# DriverPCB.net
KiCad netlist of a schematic drawn in Altium Designer
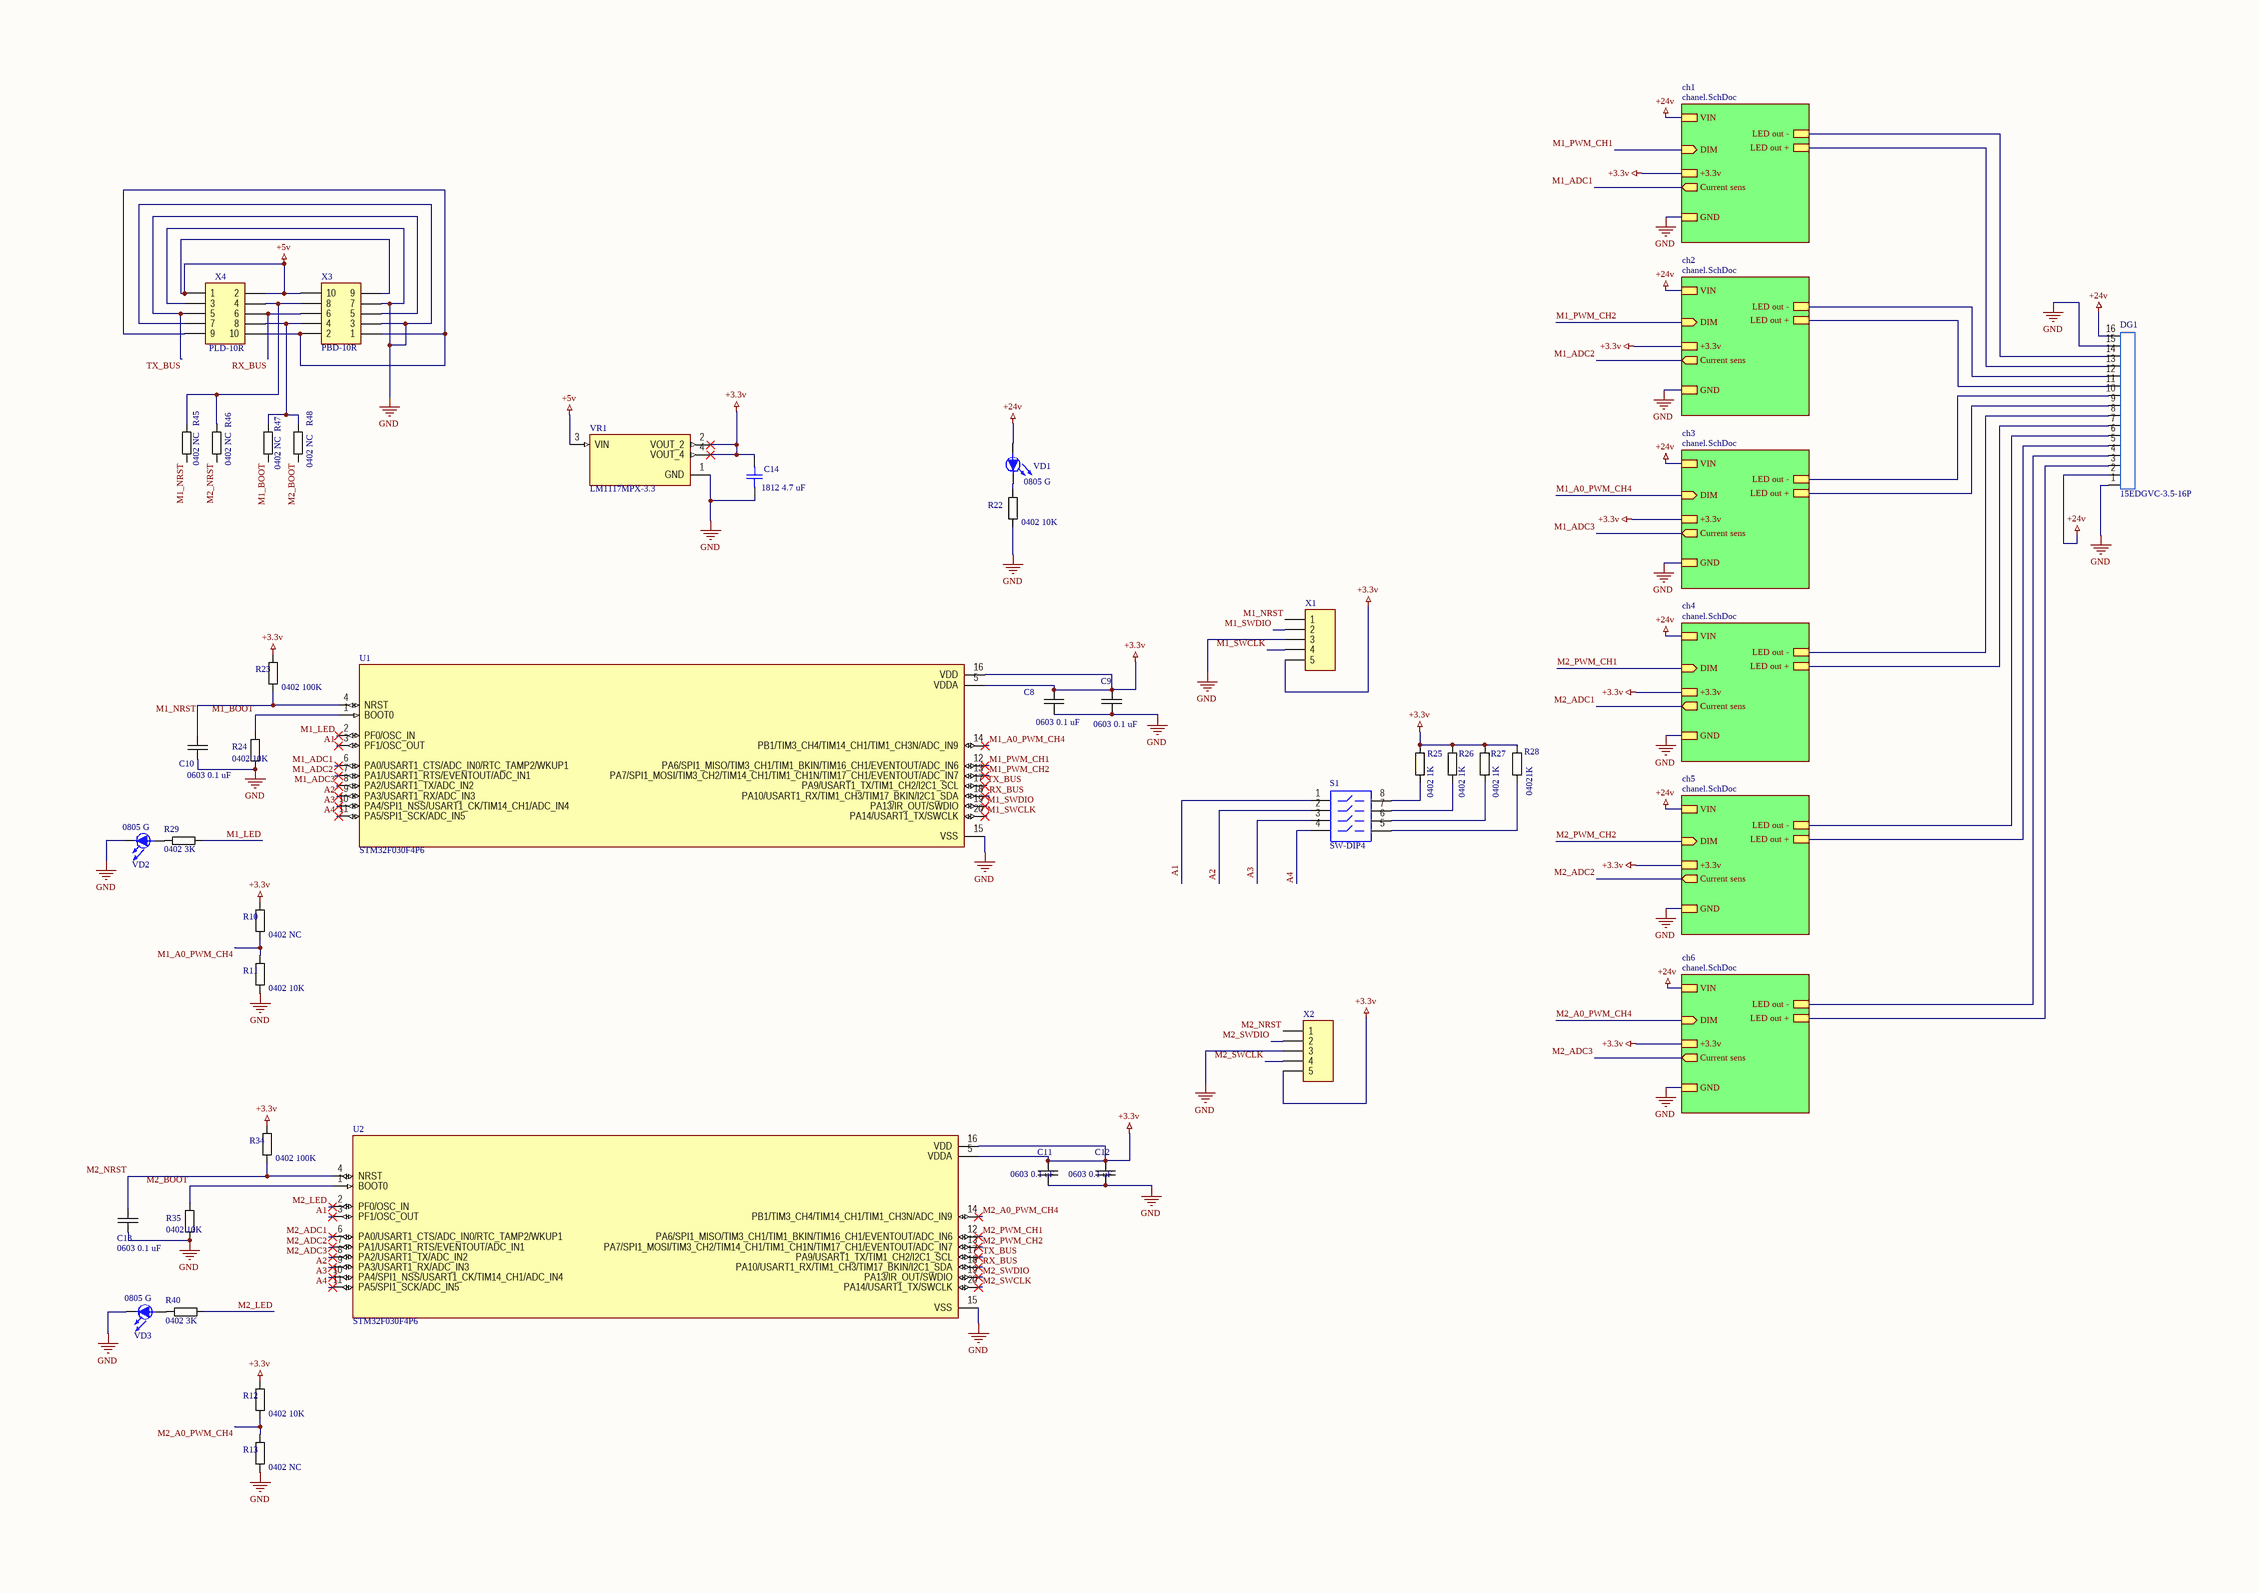
[diagram p0: DriverPCB.SchDoc]

(export (version "E")
  (design (tool "Eeschema 10.0.6"))
  (components
    (comp (ref "C8")
      (value "0603 0.1 uF")
      (footprint "CAPACITOR 0603")
      (description "Ceramic Capacitor")
      (libsource (lib "Maks_lib") (part "Capasitor"))
    )
    (comp (ref "C9")
      (value "0603 0.1 uF")
      (footprint "CAPACITOR 0603")
      (description "Ceramic Capacitor")
      (libsource (lib "Maks_lib") (part "Capasitor"))
    )
    (comp (ref "C10")
      (value "0603 0.1 uF")
      (footprint "CAPACITOR 0603")
      (description "Ceramic Capacitor")
      (libsource (lib "Maks_lib") (part "Capasitor"))
    )
    (comp (ref "C11")
      (value "0603 0.1 uF")
      (footprint "CAPACITOR 0603")
      (description "Ceramic Capacitor")
      (libsource (lib "Maks_lib") (part "Capasitor"))
    )
    (comp (ref "C12")
      (value "0603 0.1 uF")
      (footprint "CAPACITOR 0603")
      (description "Ceramic Capacitor")
      (libsource (lib "Maks_lib") (part "Capasitor"))
    )
    (comp (ref "C13")
      (value "0603 0.1 uF")
      (footprint "CAPACITOR 0603")
      (description "Ceramic Capacitor")
      (libsource (lib "Maks_lib") (part "Capasitor"))
    )
    (comp (ref "C14")
      (value "1812 4.7 uF")
      (footprint "CAPCHIP1812")
      (description "Ceramic Capacitor")
      (libsource (lib "RCL") (part "Cap C"))
    )
    (comp (ref "DG1")
      (value "15EDGVC-3.5-16P")
      (footprint "15EDGVC-3.5-16P")
      (libsource (lib "Degson") (part "15EDGVC-3.5-16P"))
    )
    (comp (ref "R10")
      (value "0402 NC")
      (footprint "Resistor 0402")
      (description "Resistor")
      (libsource (lib "Maks_lib") (part "Resistor"))
    )
    (comp (ref "R11")
      (value "0402 10K")
      (footprint "Resistor 0402")
      (description "Resistor")
      (libsource (lib "Maks_lib") (part "Resistor"))
    )
    (comp (ref "R12")
      (value "0402 10K")
      (footprint "Resistor 0402")
      (description "Resistor")
      (libsource (lib "Maks_lib") (part "Resistor"))
    )
    (comp (ref "R13")
      (value "0402 NC")
      (footprint "Resistor 0402")
      (description "Resistor")
      (libsource (lib "Maks_lib") (part "Resistor"))
    )
    (comp (ref "R22")
      (value "0402 10K")
      (footprint "Resistor 0402")
      (description "Resistor")
      (libsource (lib "Maks_lib") (part "Resistor"))
    )
    (comp (ref "R23")
      (value "0402 100K")
      (footprint "Resistor 0402")
      (description "Resistor")
      (libsource (lib "Maks_lib") (part "Resistor"))
    )
    (comp (ref "R24")
      (value "0402 10K")
      (footprint "Resistor 0402")
      (description "Resistor")
      (libsource (lib "Maks_lib") (part "Resistor"))
    )
    (comp (ref "R25")
      (value "0402 1K")
      (footprint "Resistor 0402")
      (description "Resistor")
      (libsource (lib "Maks_lib") (part "Resistor"))
    )
    (comp (ref "R26")
      (value "0402 1K")
      (footprint "Resistor 0402")
      (description "Resistor")
      (libsource (lib "Maks_lib") (part "Resistor"))
    )
    (comp (ref "R27")
      (value "0402 1K")
      (footprint "Resistor 0402")
      (description "Resistor")
      (libsource (lib "Maks_lib") (part "Resistor"))
    )
    (comp (ref "R28")
      (value "04021K")
      (footprint "Resistor 0402")
      (description "Resistor")
      (libsource (lib "Maks_lib") (part "Resistor"))
    )
    (comp (ref "R29")
      (value "0402 3K")
      (footprint "Resistor 0402")
      (description "Resistor")
      (libsource (lib "Maks_lib") (part "Resistor"))
    )
    (comp (ref "R34")
      (value "0402 100K")
      (footprint "Resistor 0402")
      (description "Resistor")
      (libsource (lib "Maks_lib") (part "Resistor"))
    )
    (comp (ref "R35")
      (value "0402 10K")
      (footprint "Resistor 0402")
      (description "Resistor")
      (libsource (lib "Maks_lib") (part "Resistor"))
    )
    (comp (ref "R40")
      (value "0402 3K")
      (footprint "Resistor 0402")
      (description "Resistor")
      (libsource (lib "Maks_lib") (part "Resistor"))
    )
    (comp (ref "R45")
      (value "0402 NC")
      (footprint "Resistor 0402")
      (description "Resistor")
      (libsource (lib "Maks_lib") (part "Resistor"))
    )
    (comp (ref "R46")
      (value "0402 NC")
      (footprint "Resistor 0402")
      (description "Resistor")
      (libsource (lib "Maks_lib") (part "Resistor"))
    )
    (comp (ref "R47")
      (value "0402 NC")
      (footprint "Resistor 0402")
      (description "Resistor")
      (libsource (lib "Maks_lib") (part "Resistor"))
    )
    (comp (ref "R48")
      (value "0402 NC")
      (footprint "Resistor 0402")
      (description "Resistor")
      (libsource (lib "Maks_lib") (part "Resistor"))
    )
    (comp (ref "S1")
      (value "SW-DIP4")
      (footprint "DIP-8")
      (description "DIP Switch")
      (fields (field (name "PUBLISHER") "Altium Limited"))
      (libsource (lib "Miscellaneous Devices") (part "SW-DIP4"))
    )
    (comp (ref "U1")
      (value "STM32F030F4P6")
      (footprint "SOP65P640X120-20N")
      (description "MCU 32-bit STM32F ARM Cortex M0 RISC 16KB Flash 2.5V/3.3V 20-Pin TSSOP Tray")
      (libsource (lib "STM32F030F4P6") (part "STM32F030F4P6"))
    )
    (comp (ref "U2")
      (value "STM32F030F4P6")
      (footprint "SOP65P640X120-20N")
      (description "MCU 32-bit STM32F ARM Cortex M0 RISC 16KB Flash 2.5V/3.3V 20-Pin TSSOP Tray")
      (libsource (lib "STM32F030F4P6") (part "STM32F030F4P6"))
    )
    (comp (ref "VD1")
      (value "0805 G")
      (footprint "0805-")
      (description "Green")
      (libsource (lib "DT") (part "LED SMD"))
    )
    (comp (ref "VD2")
      (value "0805 G")
      (footprint "0805-")
      (description "Green")
      (libsource (lib "DT") (part "LED SMD"))
    )
    (comp (ref "VD3")
      (value "0805 G")
      (footprint "0805-")
      (description "Green")
      (libsource (lib "DT") (part "LED SMD"))
    )
    (comp (ref "VR1")
      (value "LM1117MPX-3.3")
      (footprint "VREG_LM1117MPX-3.3")
      (description "800-mA 15-V linear voltage regulator")
      (fields (field (name "MF") "Texas Instruments"))
      (libsource (lib "LM1117MPX-3.3") (part "LM1117MPX-3.3"))
    )
    (comp (ref "X1")
      (value "~")
      (footprint "PLS-5-3D")
      (description "Header, 5-Pin")
      (fields (field (name "PARTNUMBER") "PLS-5"))
      (libsource (lib "AX_Altium_v2.3") (part "PLS-5"))
    )
    (comp (ref "X2")
      (value "~")
      (footprint "PLS-5-3D")
      (description "Header, 5-Pin")
      (fields (field (name "PARTNUMBER") "PLS-5"))
      (libsource (lib "AX_Altium_v2.3") (part "PLS-5"))
    )
    (comp (ref "X3")
      (value "PBD-10R")
      (footprint "PBD-10RR")
      (description "Header, 5-Pin, Dual row")
      (libsource (lib "AX_Altium_v2.3") (part "PBD-10R"))
    )
    (comp (ref "X4")
      (value "PLD-10R")
      (footprint "PLD-10RR2")
      (description "Header, 5-Pin, Dual row")
      (libsource (lib "AX_Altium_v2.3") (part "PLD-10R"))
    )
  )
  (nets
    (net (code "1") (name "+3.3v") (class "Default")
      (node (ref "C11") (pin "1") (pinfunction "1_1") (pintype "passive"))
      (node (ref "C12") (pin "1") (pinfunction "1_1") (pintype "passive"))
      (node (ref "C14") (pin "2") (pinfunction "2_2") (pintype "passive"))
      (node (ref "C8") (pin "1") (pinfunction "1_1") (pintype "passive"))
      (node (ref "C9") (pin "1") (pinfunction "1_1") (pintype "passive"))
      (node (ref "R10") (pin "2") (pinfunction "2_2") (pintype "passive"))
      (node (ref "R12") (pin "2") (pinfunction "2_2") (pintype "passive"))
      (node (ref "R23") (pin "2") (pinfunction "2_2") (pintype "passive"))
      (node (ref "R25") (pin "1") (pinfunction "1_1") (pintype "passive"))
      (node (ref "R26") (pin "1") (pinfunction "1_1") (pintype "passive"))
      (node (ref "R27") (pin "1") (pinfunction "1_1") (pintype "passive"))
      (node (ref "R28") (pin "1") (pinfunction "1_1") (pintype "passive"))
      (node (ref "R34") (pin "2") (pinfunction "2_2") (pintype "passive"))
      (node (ref "U1") (pin "16") (pinfunction "VDD_16") (pintype "power_in"))
      (node (ref "U1") (pin "5") (pinfunction "VDDA_5") (pintype "power_in"))
      (node (ref "U2") (pin "16") (pinfunction "VDD_16") (pintype "power_in"))
      (node (ref "U2") (pin "5") (pinfunction "VDDA_5") (pintype "power_in"))
      (node (ref "VR1") (pin "2") (pinfunction "VOUT_2_2") (pintype "output"))
      (node (ref "VR1") (pin "4") (pinfunction "VOUT_4_4") (pintype "output"))
      (node (ref "X1") (pin "5") (pinfunction "5_5") (pintype "passive"))
      (node (ref "X2") (pin "5") (pinfunction "5_5") (pintype "passive"))
    )
    (net (code "2") (name "+5v") (class "Default")
      (node (ref "VR1") (pin "3") (pinfunction "VIN_3") (pintype "input"))
      (node (ref "X3") (pin "10") (pinfunction "10_10") (pintype "passive"))
      (node (ref "X3") (pin "9") (pinfunction "9_9") (pintype "passive"))
      (node (ref "X4") (pin "1") (pinfunction "1_1") (pintype "passive"))
      (node (ref "X4") (pin "2") (pinfunction "2_2") (pintype "passive"))
    )
    (net (code "3") (name "+24v") (class "Default")
      (node (ref "DG1") (pin "16") (pintype "passive"))
      (node (ref "DG1") (pin "2") (pintype "passive"))
      (node (ref "VD1") (pin "A") (pinfunction "a_A") (pintype "passive"))
    )
    (net (code "4") (name "/A1") (class "Default")
      (node (ref "S1") (pin "1") (pinfunction "1_1") (pintype "passive"))
      (node (ref "U1") (pin "3") (pinfunction "PF1/OSC_OUT_3") (pintype "bidirectional"))
      (node (ref "U2") (pin "3") (pinfunction "PF1/OSC_OUT_3") (pintype "bidirectional"))
    )
    (net (code "5") (name "/A2") (class "Default")
      (node (ref "S1") (pin "2") (pinfunction "2_2") (pintype "passive"))
      (node (ref "U1") (pin "9") (pinfunction "PA3/USART1_RX/ADC_IN3_9") (pintype "bidirectional"))
      (node (ref "U2") (pin "9") (pinfunction "PA3/USART1_RX/ADC_IN3_9") (pintype "bidirectional"))
    )
    (net (code "6") (name "/A3") (class "Default")
      (node (ref "S1") (pin "3") (pinfunction "3_3") (pintype "passive"))
      (node (ref "U1") (pin "10") (pinfunction "PA4/SPI1_NSS/USART1_CK/TIM14_CH1/ADC_IN4_10") (pintype "bidirectional"))
      (node (ref "U2") (pin "10") (pinfunction "PA4/SPI1_NSS/USART1_CK/TIM14_CH1/ADC_IN4_10") (pintype "bidirectional"))
    )
    (net (code "7") (name "/A4") (class "Default")
      (node (ref "S1") (pin "4") (pinfunction "4_4") (pintype "passive"))
      (node (ref "U1") (pin "11") (pinfunction "PA5/SPI1_SCK/ADC_IN5_11") (pintype "bidirectional"))
      (node (ref "U2") (pin "11") (pinfunction "PA5/SPI1_SCK/ADC_IN5_11") (pintype "bidirectional"))
    )
    (net (code "10") (name "/LED out +") (class "Default") (node (ref "DG1") (pin "5") (pintype "passive")))
    (net (code "11") (name "/LED out +_1") (class "Default") (node (ref "DG1") (pin "3") (pintype "passive")))
    (net (code "12") (name "/LED out +_2") (class "Default")
      (node (ref "DG1") (pin "11") (pintype "passive"))
    )
    (net (code "13") (name "/LED out +_3") (class "Default")
      (node (ref "DG1") (pin "13") (pintype "passive"))
    )
    (net (code "14") (name "/LED out +_4") (class "Default") (node (ref "DG1") (pin "9") (pintype "passive")))
    (net (code "15") (name "/LED out +_5") (class "Default") (node (ref "DG1") (pin "7") (pintype "passive")))
    (net (code "16") (name "/LED out -") (class "Default") (node (ref "DG1") (pin "6") (pintype "passive")))
    (net (code "17") (name "/LED out -_1") (class "Default") (node (ref "DG1") (pin "4") (pintype "passive")))
    (net (code "18") (name "/LED out -_2") (class "Default")
      (node (ref "DG1") (pin "12") (pintype "passive"))
    )
    (net (code "19") (name "/LED out -_3") (class "Default")
      (node (ref "DG1") (pin "14") (pintype "passive"))
    )
    (net (code "20") (name "/LED out -_4") (class "Default")
      (node (ref "DG1") (pin "10") (pintype "passive"))
    )
    (net (code "21") (name "/LED out -_5") (class "Default") (node (ref "DG1") (pin "8") (pintype "passive")))
    (net (code "22") (name "/M1_A0_PWM_CH4") (class "Default")
      (node (ref "R10") (pin "1") (pinfunction "1_1") (pintype "passive"))
      (node (ref "R11") (pin "2") (pinfunction "2_2") (pintype "passive"))
      (node (ref "U1") (pin "14") (pinfunction "PB1/TIM3_CH4/TIM14_CH1/TIM1_CH3N/ADC_IN9_14") (pintype "bidirectional"))
    )
    (net (code "23") (name "/M1_ADC1") (class "Default")
      (node (ref "U1") (pin "6") (pinfunction "PA0/USART1_CTS/ADC_IN0/RTC_TAMP2/WKUP1_6") (pintype "bidirectional+no_connect"))
    )
    (net (code "24") (name "/M1_ADC2") (class "Default")
      (node (ref "U1") (pin "7") (pinfunction "PA1/USART1_RTS/EVENTOUT/ADC_IN1_7") (pintype "bidirectional+no_connect"))
    )
    (net (code "25") (name "/M1_ADC3") (class "Default")
      (node (ref "U1") (pin "8") (pinfunction "PA2/USART1_TX/ADC_IN2_8") (pintype "bidirectional+no_connect"))
    )
    (net (code "26") (name "/M1_BOOT") (class "Default")
      (node (ref "R24") (pin "1") (pinfunction "1_1") (pintype "passive"))
      (node (ref "R47") (pin "2") (pinfunction "2_2") (pintype "passive"))
      (node (ref "U1") (pin "1") (pinfunction "BOOT0_1") (pintype "input"))
    )
    (net (code "27") (name "/M1_LED") (class "Default")
      (node (ref "R29") (pin "1") (pinfunction "1_1") (pintype "passive"))
      (node (ref "U1") (pin "2") (pinfunction "PF0/OSC_IN_2") (pintype "bidirectional"))
    )
    (net (code "28") (name "/M1_NRST") (class "Default")
      (node (ref "C10") (pin "2") (pinfunction "2_2") (pintype "passive"))
      (node (ref "R23") (pin "1") (pinfunction "1_1") (pintype "passive"))
      (node (ref "R45") (pin "2") (pinfunction "2_2") (pintype "passive"))
      (node (ref "U1") (pin "4") (pinfunction "NRST_4") (pintype "bidirectional"))
      (node (ref "X1") (pin "1") (pinfunction "1_1") (pintype "passive"))
    )
    (net (code "29") (name "/M1_PWM_CH1") (class "Default")
      (node (ref "U1") (pin "12") (pinfunction "PA6/SPI1_MISO/TIM3_CH1/TIM1_BKIN/TIM16_CH1/EVENTOUT/ADC_IN6_12") (pintype "bidirectional+no_connect"))
    )
    (net (code "30") (name "/M1_PWM_CH2") (class "Default")
      (node (ref "U1") (pin "13") (pinfunction "PA7/SPI1_MOSI/TIM3_CH2/TIM14_CH1/TIM1_CH1N/TIM17_CH1/EVENTOUT/ADC_IN7_13") (pintype "bidirectional+no_connect"))
    )
    (net (code "31") (name "/M1_SWCLK") (class "Default")
      (node (ref "U1") (pin "20") (pinfunction "PA14/USART1_TX/SWCLK_20") (pintype "bidirectional"))
      (node (ref "X1") (pin "4") (pinfunction "4_4") (pintype "passive"))
    )
    (net (code "32") (name "/M1_SWDIO") (class "Default")
      (node (ref "U1") (pin "19") (pinfunction "PA13/IR_OUT/SWDIO_19") (pintype "bidirectional"))
      (node (ref "X1") (pin "2") (pinfunction "2_2") (pintype "passive"))
    )
    (net (code "33") (name "/M2_A0_PWM_CH4") (class "Default")
      (node (ref "R12") (pin "1") (pinfunction "1_1") (pintype "passive"))
      (node (ref "R13") (pin "2") (pinfunction "2_2") (pintype "passive"))
      (node (ref "U2") (pin "14") (pinfunction "PB1/TIM3_CH4/TIM14_CH1/TIM1_CH3N/ADC_IN9_14") (pintype "bidirectional"))
    )
    (net (code "34") (name "/M2_ADC1") (class "Default")
      (node (ref "U2") (pin "6") (pinfunction "PA0/USART1_CTS/ADC_IN0/RTC_TAMP2/WKUP1_6") (pintype "bidirectional+no_connect"))
    )
    (net (code "35") (name "/M2_ADC2") (class "Default")
      (node (ref "U2") (pin "7") (pinfunction "PA1/USART1_RTS/EVENTOUT/ADC_IN1_7") (pintype "bidirectional+no_connect"))
    )
    (net (code "36") (name "/M2_ADC3") (class "Default")
      (node (ref "U2") (pin "8") (pinfunction "PA2/USART1_TX/ADC_IN2_8") (pintype "bidirectional+no_connect"))
    )
    (net (code "37") (name "/M2_BOOT") (class "Default")
      (node (ref "R35") (pin "1") (pinfunction "1_1") (pintype "passive"))
      (node (ref "R48") (pin "2") (pinfunction "2_2") (pintype "passive"))
      (node (ref "U2") (pin "1") (pinfunction "BOOT0_1") (pintype "input"))
    )
    (net (code "38") (name "/M2_LED") (class "Default")
      (node (ref "R40") (pin "1") (pinfunction "1_1") (pintype "passive"))
      (node (ref "U2") (pin "2") (pinfunction "PF0/OSC_IN_2") (pintype "bidirectional"))
    )
    (net (code "39") (name "/M2_NRST") (class "Default")
      (node (ref "C13") (pin "2") (pinfunction "2_2") (pintype "passive"))
      (node (ref "R34") (pin "1") (pinfunction "1_1") (pintype "passive"))
      (node (ref "R46") (pin "2") (pinfunction "2_2") (pintype "passive"))
      (node (ref "U2") (pin "4") (pinfunction "NRST_4") (pintype "bidirectional"))
      (node (ref "X2") (pin "1") (pinfunction "1_1") (pintype "passive"))
    )
    (net (code "40") (name "/M2_PWM_CH1") (class "Default")
      (node (ref "U2") (pin "12") (pinfunction "PA6/SPI1_MISO/TIM3_CH1/TIM1_BKIN/TIM16_CH1/EVENTOUT/ADC_IN6_12") (pintype "bidirectional+no_connect"))
    )
    (net (code "41") (name "/M2_PWM_CH2") (class "Default")
      (node (ref "U2") (pin "13") (pinfunction "PA7/SPI1_MOSI/TIM3_CH2/TIM14_CH1/TIM1_CH1N/TIM17_CH1/EVENTOUT/ADC_IN7_13") (pintype "bidirectional+no_connect"))
    )
    (net (code "42") (name "/M2_SWCLK") (class "Default")
      (node (ref "U2") (pin "20") (pinfunction "PA14/USART1_TX/SWCLK_20") (pintype "bidirectional"))
      (node (ref "X2") (pin "4") (pinfunction "4_4") (pintype "passive"))
    )
    (net (code "43") (name "/M2_SWDIO") (class "Default")
      (node (ref "U2") (pin "19") (pinfunction "PA13/IR_OUT/SWDIO_19") (pintype "bidirectional"))
      (node (ref "X2") (pin "2") (pinfunction "2_2") (pintype "passive"))
    )
    (net (code "44") (name "/RX_BUS") (class "Default")
      (node (ref "U1") (pin "18") (pinfunction "PA10/USART1_RX/TIM1_CH3/TIM17_BKIN/I2C1_SDA_18") (pintype "bidirectional"))
      (node (ref "U2") (pin "18") (pinfunction "PA10/USART1_RX/TIM1_CH3/TIM17_BKIN/I2C1_SDA_18") (pintype "bidirectional"))
      (node (ref "X3") (pin "6") (pinfunction "6_6") (pintype "passive"))
      (node (ref "X4") (pin "6") (pinfunction "6_6") (pintype "passive"))
    )
    (net (code "45") (name "/TX_BUS") (class "Default")
      (node (ref "U1") (pin "17") (pinfunction "PA9/USART1_TX/TIM1_CH2/I2C1_SCL_17") (pintype "bidirectional"))
      (node (ref "U2") (pin "17") (pinfunction "PA9/USART1_TX/TIM1_CH2/I2C1_SCL_17") (pintype "bidirectional"))
      (node (ref "X3") (pin "5") (pinfunction "5_5") (pintype "passive"))
      (node (ref "X4") (pin "5") (pinfunction "5_5") (pintype "passive"))
    )
    (net (code "46") (name "GND") (class "Default")
      (node (ref "C10") (pin "1") (pinfunction "1_1") (pintype "passive"))
      (node (ref "C11") (pin "2") (pinfunction "2_2") (pintype "passive"))
      (node (ref "C12") (pin "2") (pinfunction "2_2") (pintype "passive"))
      (node (ref "C13") (pin "1") (pinfunction "1_1") (pintype "passive"))
      (node (ref "C14") (pin "1") (pinfunction "1_1") (pintype "passive"))
      (node (ref "C8") (pin "2") (pinfunction "2_2") (pintype "passive"))
      (node (ref "C9") (pin "2") (pinfunction "2_2") (pintype "passive"))
      (node (ref "DG1") (pin "1") (pintype "passive"))
      (node (ref "DG1") (pin "15") (pintype "passive"))
      (node (ref "R11") (pin "1") (pinfunction "1_1") (pintype "passive"))
      (node (ref "R13") (pin "1") (pinfunction "1_1") (pintype "passive"))
      (node (ref "R22") (pin "1") (pinfunction "1_1") (pintype "passive"))
      (node (ref "R24") (pin "2") (pinfunction "2_2") (pintype "passive"))
      (node (ref "R35") (pin "2") (pinfunction "2_2") (pintype "passive"))
      (node (ref "U1") (pin "15") (pinfunction "VSS_15") (pintype "power_in"))
      (node (ref "U2") (pin "15") (pinfunction "VSS_15") (pintype "power_in"))
      (node (ref "VD2") (pin "K") (pinfunction "k_K") (pintype "passive"))
      (node (ref "VD3") (pin "K") (pinfunction "k_K") (pintype "passive"))
      (node (ref "VR1") (pin "1") (pinfunction "GND_1") (pintype "power_in"))
      (node (ref "X1") (pin "3") (pinfunction "3_3") (pintype "passive"))
      (node (ref "X2") (pin "3") (pinfunction "3_3") (pintype "passive"))
      (node (ref "X3") (pin "3") (pinfunction "3_3") (pintype "passive"))
      (node (ref "X3") (pin "7") (pinfunction "7_7") (pintype "passive"))
      (node (ref "X4") (pin "3") (pinfunction "3_3") (pintype "passive"))
      (node (ref "X4") (pin "7") (pinfunction "7_7") (pintype "passive"))
    )
    (net (code "47") (name "Net-(R25-Pad2)") (class "Default")
      (node (ref "R25") (pin "2") (pinfunction "2_2") (pintype "passive"))
      (node (ref "S1") (pin "8") (pinfunction "8_8") (pintype "passive"))
    )
    (net (code "48") (name "Net-(R26-Pad2)") (class "Default")
      (node (ref "R26") (pin "2") (pinfunction "2_2") (pintype "passive"))
      (node (ref "S1") (pin "7") (pinfunction "7_7") (pintype "passive"))
    )
    (net (code "49") (name "Net-(R27-Pad2)") (class "Default")
      (node (ref "R27") (pin "2") (pinfunction "2_2") (pintype "passive"))
      (node (ref "S1") (pin "6") (pinfunction "6_6") (pintype "passive"))
    )
    (net (code "50") (name "Net-(R28-Pad2)") (class "Default")
      (node (ref "R28") (pin "2") (pinfunction "2_2") (pintype "passive"))
      (node (ref "S1") (pin "5") (pinfunction "5_5") (pintype "passive"))
    )
    (net (code "51") (name "Net-(R45-Pad1)") (class "Default")
      (node (ref "R45") (pin "1") (pinfunction "1_1") (pintype "passive"))
      (node (ref "R46") (pin "1") (pinfunction "1_1") (pintype "passive"))
      (node (ref "X3") (pin "8") (pinfunction "8_8") (pintype "passive"))
      (node (ref "X4") (pin "4") (pinfunction "4_4") (pintype "passive"))
    )
    (net (code "52") (name "Net-(R47-Pad1)") (class "Default")
      (node (ref "R47") (pin "1") (pinfunction "1_1") (pintype "passive"))
      (node (ref "R48") (pin "1") (pinfunction "1_1") (pintype "passive"))
      (node (ref "X3") (pin "4") (pinfunction "4_4") (pintype "passive"))
      (node (ref "X4") (pin "8") (pinfunction "8_8") (pintype "passive"))
    )
    (net (code "53") (name "Net-(VD1-k)") (class "Default")
      (node (ref "R22") (pin "2") (pinfunction "2_2") (pintype "passive"))
      (node (ref "VD1") (pin "K") (pinfunction "k_K") (pintype "passive"))
    )
    (net (code "54") (name "Net-(VD2-a)") (class "Default")
      (node (ref "R29") (pin "2") (pinfunction "2_2") (pintype "passive"))
      (node (ref "VD2") (pin "A") (pinfunction "a_A") (pintype "passive"))
    )
    (net (code "55") (name "Net-(VD3-a)") (class "Default")
      (node (ref "R40") (pin "2") (pinfunction "2_2") (pintype "passive"))
      (node (ref "VD3") (pin "A") (pinfunction "a_A") (pintype "passive"))
    )
    (net (code "56") (name "Net-(X3-Pad1)") (class "Default")
      (node (ref "X3") (pin "1") (pinfunction "1_1") (pintype "passive"))
      (node (ref "X3") (pin "2") (pinfunction "2_2") (pintype "passive"))
      (node (ref "X4") (pin "10") (pinfunction "10_10") (pintype "passive"))
      (node (ref "X4") (pin "9") (pinfunction "9_9") (pintype "passive"))
    )
  )
)
